# gbg_base_revb.net
KiCad netlist of a schematic drawn in EAGLE
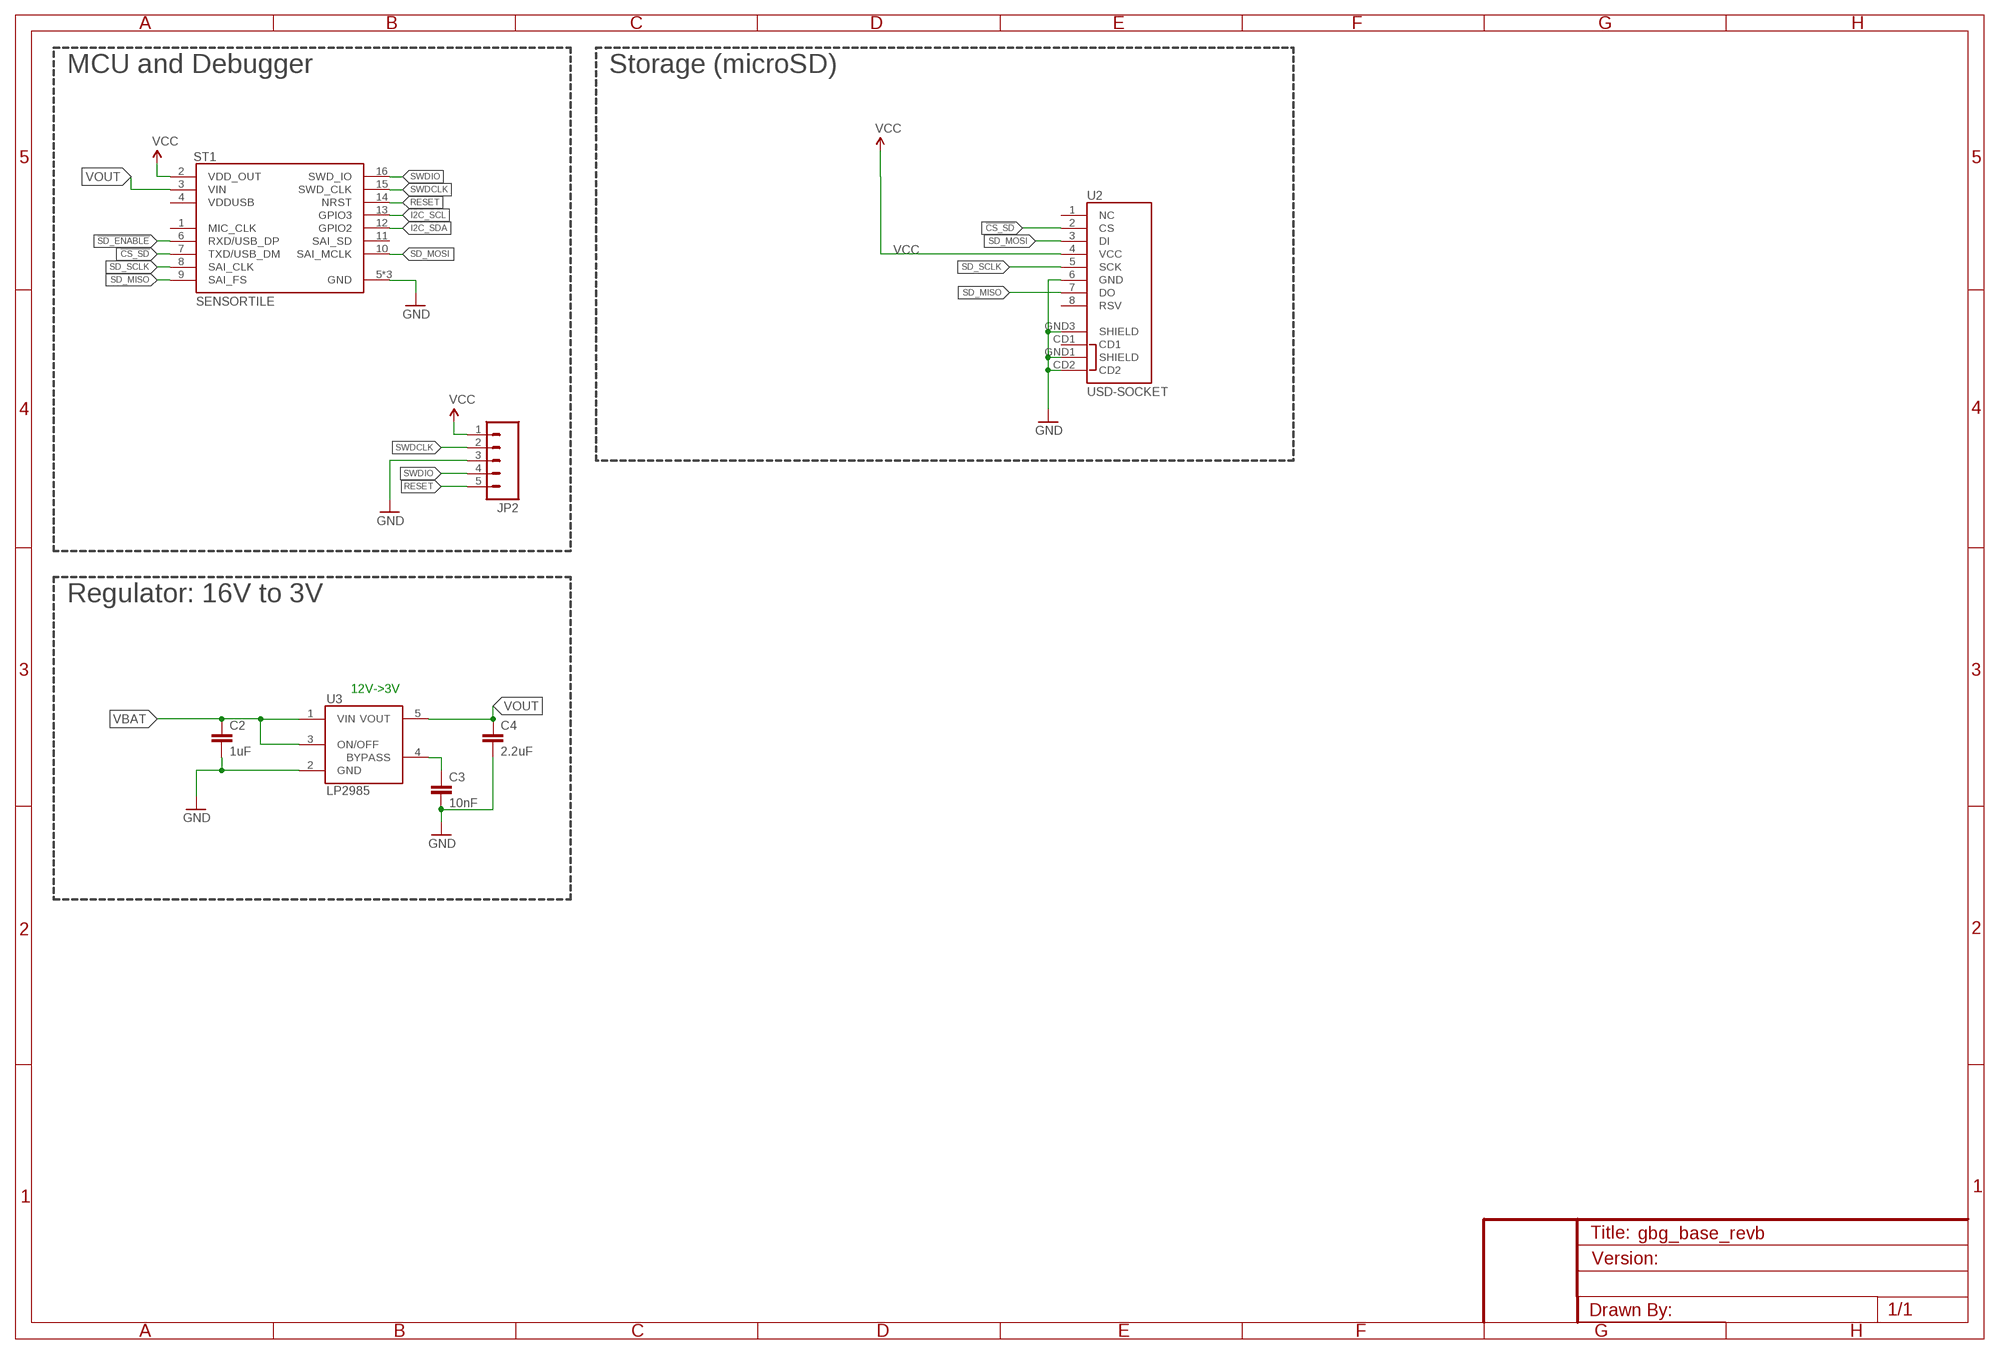
[diagram p0: schematic, sheet 1]

(export (version "E")
  (design (tool "Eeschema 10.0.6"))
  (components
    (comp (ref "C2")
      (value "1uF")
      (footprint "eagle-import:0603")
      (libsource (lib "eagle-import") (part "C-EU0603"))
    )
    (comp (ref "C3")
      (value "10nF")
      (footprint "eagle-import:0603")
      (libsource (lib "eagle-import") (part "C-EU0603"))
    )
    (comp (ref "C4")
      (value "2.2uF")
      (footprint "eagle-import:0603")
      (libsource (lib "eagle-import") (part "C-EU0603"))
    )
    (comp (ref "JP2")
      (value "M05LOCK")
      (footprint "eagle-import:1X05_LOCK")
      (libsource (lib "eagle-import") (part "M05LOCK"))
    )
    (comp (ref "ST1")
      (value "SENSORTILE")
      (footprint "eagle-import:SENSORTILE")
      (libsource (lib "eagle-import") (part "SENSORTILE"))
    )
    (comp (ref "U2")
      (value "USD-SOCKET")
      (footprint "eagle-import:MICROSD_1_1")
      (libsource (lib "eagle-import") (part "USD-SOCKET"))
    )
    (comp (ref "U3")
      (value "LP2985AIM5-3.3")
      (footprint "eagle-import:SOT25")
      (fields (field (name "MPN") "LP2985-30DBVR  "))
      (libsource (lib "eagle-import") (part "LP2985AIM5-3.3"))
    )
  )
  (nets
    (net (code "1") (name "/~{CS_SD}") (class "Default")
      (node (ref "ST1") (pin "7") (pinfunction "TXD/USB_DM_7") (pintype "bidirectional"))
      (node (ref "U2") (pin "2") (pinfunction "CS_2") (pintype "bidirectional"))
    )
    (net (code "2") (name "/~{SD_ENABLE}") (class "Default")
      (node (ref "ST1") (pin "6") (pinfunction "RXD/USB_DP_6") (pintype "bidirectional"))
    )
    (net (code "3") (name "GND") (class "Default")
      (node (ref "C2") (pin "2") (pinfunction "2_2") (pintype "passive"))
      (node (ref "C3") (pin "2") (pinfunction "2_2") (pintype "passive"))
      (node (ref "C4") (pin "2") (pinfunction "2_2") (pintype "passive"))
      (node (ref "JP2") (pin "3") (pinfunction "3_3") (pintype "passive"))
      (node (ref "ST1") (pin "17") (pinfunction "GND_17") (pintype "bidirectional"))
      (node (ref "ST1") (pin "18") (pinfunction "GND_18") (pintype "bidirectional"))
      (node (ref "ST1") (pin "5") (pinfunction "GND_5") (pintype "bidirectional"))
      (node (ref "U2") (pin "6") (pinfunction "GND_6") (pintype "bidirectional"))
      (node (ref "U2") (pin "CD2") (pinfunction "CD2_CD2") (pintype "bidirectional"))
      (node (ref "U2") (pin "GND1") (pinfunction "SHIELD_GND1") (pintype "bidirectional"))
      (node (ref "U2") (pin "GND3") (pinfunction "SHIELD_GND3") (pintype "bidirectional"))
      (node (ref "U3") (pin "2") (pinfunction "GND_2") (pintype "power_in"))
    )
    (net (code "4") (name "I2C_SCL") (class "Default")
      (node (ref "ST1") (pin "13") (pinfunction "GPIO3_13") (pintype "bidirectional"))
    )
    (net (code "5") (name "I2C_SDA") (class "Default")
      (node (ref "ST1") (pin "12") (pinfunction "GPIO2_12") (pintype "bidirectional"))
    )
    (net (code "6") (name "Net-(U3-BYPASS)") (class "Default")
      (node (ref "C3") (pin "1") (pinfunction "1_1") (pintype "passive"))
      (node (ref "U3") (pin "4") (pinfunction "BYPASS_4") (pintype "power_in"))
    )
    (net (code "7") (name "RESET") (class "Default")
      (node (ref "JP2") (pin "5") (pinfunction "5_5") (pintype "passive"))
      (node (ref "ST1") (pin "14") (pinfunction "NRST_14") (pintype "bidirectional"))
    )
    (net (code "8") (name "SD_MISO") (class "Default")
      (node (ref "ST1") (pin "9") (pinfunction "SAI_FS_9") (pintype "bidirectional"))
      (node (ref "U2") (pin "7") (pinfunction "DO_7") (pintype "bidirectional"))
    )
    (net (code "9") (name "SD_MOSI") (class "Default")
      (node (ref "ST1") (pin "10") (pinfunction "SAI_MCLK_10") (pintype "bidirectional"))
      (node (ref "U2") (pin "3") (pinfunction "DI_3") (pintype "bidirectional"))
    )
    (net (code "10") (name "SD_SCLK") (class "Default")
      (node (ref "ST1") (pin "8") (pinfunction "SAI_CLK_8") (pintype "bidirectional"))
      (node (ref "U2") (pin "5") (pinfunction "SCK_5") (pintype "bidirectional"))
    )
    (net (code "11") (name "SWDCLK") (class "Default")
      (node (ref "JP2") (pin "2") (pinfunction "2_2") (pintype "passive"))
      (node (ref "ST1") (pin "15") (pinfunction "SWD_CLK_15") (pintype "bidirectional"))
    )
    (net (code "12") (name "SWDIO") (class "Default")
      (node (ref "JP2") (pin "4") (pinfunction "4_4") (pintype "passive"))
      (node (ref "ST1") (pin "16") (pinfunction "SWD_IO_16") (pintype "bidirectional"))
    )
    (net (code "13") (name "VBAT") (class "Default")
      (node (ref "C2") (pin "1") (pinfunction "1_1") (pintype "passive"))
      (node (ref "U3") (pin "1") (pinfunction "VIN_1") (pintype "power_in"))
      (node (ref "U3") (pin "3") (pinfunction "ON/OFF_3") (pintype "input"))
    )
    (net (code "14") (name "VCC") (class "Default")
      (node (ref "JP2") (pin "1") (pinfunction "1_1") (pintype "passive"))
      (node (ref "ST1") (pin "2") (pinfunction "VDD_OUT_2") (pintype "bidirectional"))
      (node (ref "U2") (pin "4") (pinfunction "VCC_4") (pintype "bidirectional"))
    )
    (net (code "15") (name "VOUT") (class "Default")
      (node (ref "C4") (pin "1") (pinfunction "1_1") (pintype "passive"))
      (node (ref "ST1") (pin "3") (pinfunction "VIN_3") (pintype "bidirectional"))
      (node (ref "U3") (pin "5") (pinfunction "VOUT_5") (pintype "power_in"))
    )
    (net (code "16") (name "unconnected-(ST1-MIC_CLK-Pad1)") (class "Default")
      (node (ref "ST1") (pin "1") (pinfunction "MIC_CLK_1") (pintype "bidirectional"))
    )
    (net (code "17") (name "unconnected-(ST1-SAI_SD-Pad11)") (class "Default")
      (node (ref "ST1") (pin "11") (pinfunction "SAI_SD_11") (pintype "bidirectional"))
    )
    (net (code "18") (name "unconnected-(ST1-VDDUSB-Pad4)") (class "Default")
      (node (ref "ST1") (pin "4") (pinfunction "VDDUSB_4") (pintype "bidirectional"))
    )
    (net (code "19") (name "unconnected-(U2-NC-Pad1)") (class "Default")
      (node (ref "U2") (pin "1") (pinfunction "NC_1") (pintype "bidirectional"))
    )
    (net (code "20") (name "unconnected-(U2-PadCD1)") (class "Default")
      (node (ref "U2") (pin "CD1") (pinfunction "CD1_CD1") (pintype "bidirectional"))
    )
    (net (code "21") (name "unconnected-(U2-RSV-Pad8)") (class "Default")
      (node (ref "U2") (pin "8") (pinfunction "RSV_8") (pintype "bidirectional"))
    )
  )
)
